# EasyEDA_Circuit_and_PCB.net
KiCad netlist of a schematic drawn in EasyEDA
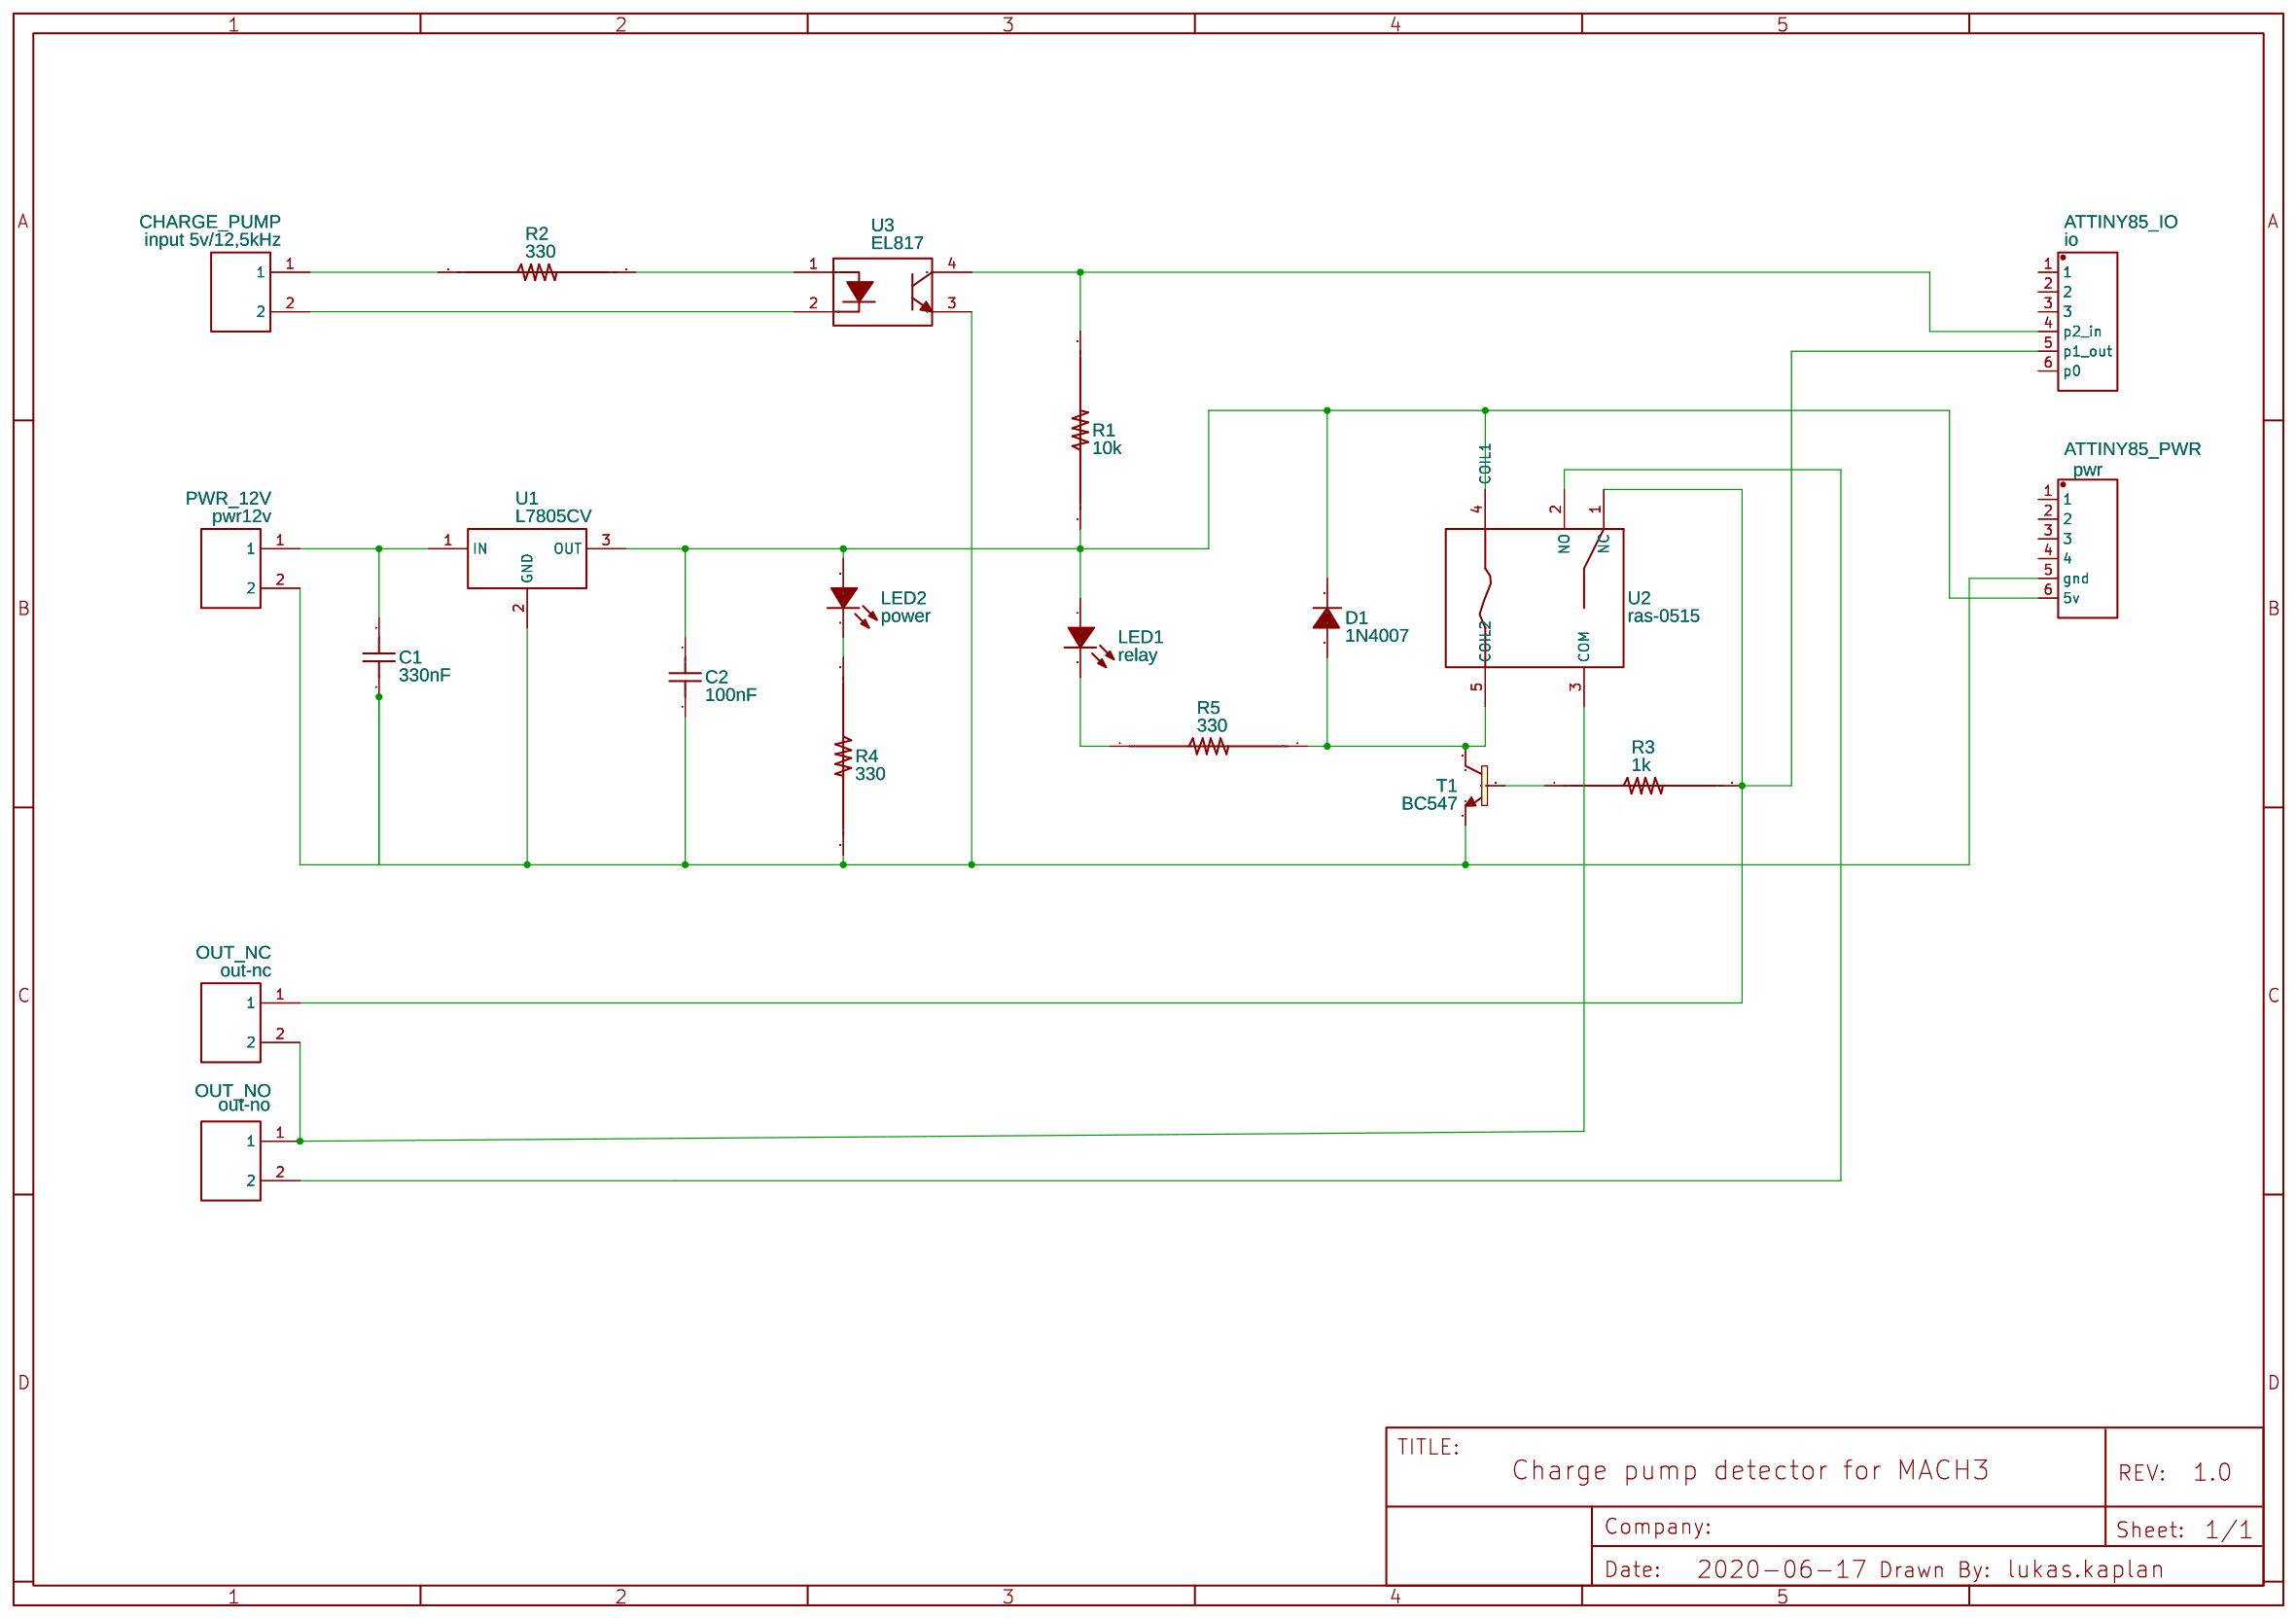
[diagram p0: schematic sheet]

(export (version "E")
  (design (tool "Eeschema 10.0.6"))
  (components
    (comp (ref "ATTINY85_IO")
      (value "io")
      (fields (field (name "BOM_Manufacturer Part") "6pin") (field (name "BOM_Supplier Part") "C350307"))
      (libsource (lib "") (part "2685Y-106CNG1SNA01"))
    )
    (comp (ref "ATTINY85_PWR")
      (value "pwr")
      (fields
        (field (name "BOM_Manufacturer Part") "2685Y-106CNG1SNA01")
        (field (name "BOM_Supplier Part") "C350307")
      )
      (libsource (lib "") (part "2685Y-106CNG1SNA01_1"))
    )
    (comp (ref "C1")
      (value "330nF")
      (fields
        (field (name "BOM_Manufacturer Part") "CT4-0805Y334M500")
        (field (name "BOM_Supplier Part") "C3784")
      )
      (libsource (lib "") (part "CT4-0805Y334M500"))
    )
    (comp (ref "C2")
      (value "100nF")
      (fields
        (field (name "BOM_Manufacturer Part") "CT4-0805Y334M500")
        (field (name "BOM_Supplier Part") "C3784")
      )
      (libsource (lib "") (part "CT4-0805Y334M500"))
    )
    (comp (ref "CHARGE_PUMP")
      (value "input 5v/12,5kHz")
      (fields
        (field (name "BOM_Manufacturer Part") "MKDSN1.5/2-5.08")
        (field (name "BOM_Supplier Part") "C91153")
      )
      (libsource (lib "") (part "MKDSN1.5/2-5.08"))
    )
    (comp (ref "D1")
      (value "1N4007")
      (fields (field (name "BOM_Supplier Part") "C106903"))
      (libsource (lib "") (part "1N4007"))
    )
    (comp (ref "LED1")
      (value "relay")
      (fields
        (field (name "BOM_Manufacturer Part") "DY-333UYGD/SN-A3(EL)")
        (field (name "BOM_Supplier Part") "C396995")
      )
      (libsource (lib "") (part "DY-333UYGD/SN-A3(EL)"))
    )
    (comp (ref "LED2")
      (value "power")
      (fields
        (field (name "BOM_Manufacturer Part") "DY-333UYGD/SN-A3(EL)")
        (field (name "BOM_Supplier Part") "C396995")
      )
      (libsource (lib "") (part "DY-333UYGD/SN-A3(EL)"))
    )
    (comp (ref "OUT_NC")
      (value "out-nc")
      (fields
        (field (name "BOM_Manufacturer Part") "MKDSN1.5/2-5.08")
        (field (name "BOM_Supplier Part") "C91153")
      )
      (libsource (lib "") (part "MKDSN1.5/2-5.08_3"))
    )
    (comp (ref "OUT_NO")
      (value "out-no")
      (fields
        (field (name "BOM_Manufacturer Part") "MKDSN1.5/2-5.08")
        (field (name "BOM_Supplier Part") "C91153")
      )
      (libsource (lib "") (part "MKDSN1.5/2-5.08_1"))
    )
    (comp (ref "PWR_12V")
      (value "pwr12v")
      (fields
        (field (name "BOM_Manufacturer Part") "MKDSN1.5/2-5.08")
        (field (name "BOM_Supplier Part") "C91153")
      )
      (libsource (lib "") (part "MKDSN1.5/2-5.08_2"))
    )
    (comp (ref "R1") (value "10k") (libsource (lib "") (part "RESISTOR_2")))
    (comp (ref "R2") (value "330") (libsource (lib "") (part "RESISTOR")))
    (comp (ref "R3") (value "1k") (libsource (lib "") (part "RESISTOR")))
    (comp (ref "R4") (value "330") (libsource (lib "") (part "RESISTOR_1")))
    (comp (ref "R5") (value "330") (libsource (lib "") (part "RESISTOR")))
    (comp (ref "T1") (value "BC547") (libsource (lib "") (part "BC547")))
    (comp (ref "U1")
      (value "L7805CV")
      (fields (field (name "BOM_Supplier Part") "C111887"))
      (libsource (lib "") (part "L7805CV"))
    )
    (comp (ref "U2") (value "ras-0515") (libsource (lib "") (part "ras-0515")))
    (comp (ref "U3")
      (value "EL817")
      (fields (field (name "BOM_Manufacturer Part") "EL817(C)-F"))
      (libsource (lib "") (part "EL817"))
    )
  )
  (nets
    (net (code "1") (name "Net-(ATTINY85_IO-p1_out)") (class "Default")
      (node (ref "ATTINY85_IO") (pin "5") (pinfunction "p1_out_5") (pintype "unspecified"))
      (node (ref "OUT_NC") (pin "1") (pinfunction "1_1") (pintype "unspecified"))
      (node (ref "R3") (pin "2") (pinfunction "2_2") (pintype "unspecified"))
      (node (ref "U2") (pin "1") (pinfunction "NC_1") (pintype "unspecified"))
    )
    (net (code "2") (name "Net-(ATTINY85_IO-p2_in)") (class "Default")
      (node (ref "ATTINY85_IO") (pin "4") (pinfunction "p2_in_4") (pintype "unspecified"))
      (node (ref "R1") (pin "2") (pinfunction "2_2") (pintype "unspecified"))
      (node (ref "U3") (pin "4") (pinfunction "COL_4") (pintype "unspecified"))
    )
    (net (code "3") (name "Net-(ATTINY85_PWR-5v)") (class "Default")
      (node (ref "ATTINY85_PWR") (pin "6") (pinfunction "5v_6") (pintype "unspecified"))
      (node (ref "C2") (pin "2") (pinfunction "2_2") (pintype "unspecified"))
      (node (ref "D1") (pin "1") (pinfunction "K_1") (pintype "unspecified"))
      (node (ref "LED1") (pin "1") (pinfunction "A_1") (pintype "unspecified"))
      (node (ref "LED2") (pin "1") (pinfunction "A_1") (pintype "unspecified"))
      (node (ref "R1") (pin "1") (pinfunction "1_1") (pintype "unspecified"))
      (node (ref "U1") (pin "3") (pinfunction "OUT_3") (pintype "passive"))
      (node (ref "U2") (pin "4") (pinfunction "COIL1_4") (pintype "unspecified"))
    )
    (net (code "4") (name "Net-(ATTINY85_PWR-gnd)") (class "Default")
      (node (ref "ATTINY85_PWR") (pin "5") (pinfunction "gnd_5") (pintype "unspecified"))
      (node (ref "C1") (pin "1") (pinfunction "1_1") (pintype "unspecified"))
      (node (ref "C2") (pin "1") (pinfunction "1_1") (pintype "unspecified"))
      (node (ref "PWR_12V") (pin "2") (pinfunction "2_2") (pintype "unspecified"))
      (node (ref "R4") (pin "2") (pinfunction "2_2") (pintype "unspecified"))
      (node (ref "T1") (pin "1") (pinfunction "E_1") (pintype "bidirectional"))
      (node (ref "U1") (pin "2") (pinfunction "GND_2") (pintype "passive"))
      (node (ref "U3") (pin "3") (pinfunction "EM_3") (pintype "unspecified"))
    )
    (net (code "5") (name "Net-(CHARGE_PUMP-Pad1)") (class "Default")
      (node (ref "CHARGE_PUMP") (pin "1") (pinfunction "1_1") (pintype "unspecified"))
      (node (ref "R2") (pin "1") (pinfunction "1_1") (pintype "unspecified"))
    )
    (net (code "6") (name "Net-(D1-A)") (class "Default")
      (node (ref "D1") (pin "2") (pinfunction "A_2") (pintype "unspecified"))
      (node (ref "R5") (pin "2") (pinfunction "2_2") (pintype "unspecified"))
      (node (ref "T1") (pin "3") (pinfunction "C_3") (pintype "bidirectional"))
      (node (ref "U2") (pin "5") (pinfunction "COIL2_5") (pintype "unspecified"))
    )
    (net (code "7") (name "Net-(LED1-K)") (class "Default")
      (node (ref "LED1") (pin "2") (pinfunction "K_2") (pintype "unspecified"))
      (node (ref "R5") (pin "1") (pinfunction "1_1") (pintype "unspecified"))
    )
    (net (code "8") (name "Net-(LED2-K)") (class "Default")
      (node (ref "LED2") (pin "2") (pinfunction "K_2") (pintype "unspecified"))
      (node (ref "R4") (pin "1") (pinfunction "1_1") (pintype "unspecified"))
    )
    (net (code "9") (name "Net-(T1-B)") (class "Default")
      (node (ref "R3") (pin "1") (pinfunction "1_1") (pintype "unspecified"))
      (node (ref "T1") (pin "2") (pinfunction "B_2") (pintype "bidirectional"))
    )
    (net (code "10") (name "Net-(U1-IN)") (class "Default")
      (node (ref "C1") (pin "2") (pinfunction "2_2") (pintype "unspecified"))
      (node (ref "PWR_12V") (pin "1") (pinfunction "1_1") (pintype "unspecified"))
      (node (ref "U1") (pin "1") (pinfunction "IN_1") (pintype "passive"))
    )
    (net (code "11") (name "Net-(U2-COM)") (class "Default")
      (node (ref "OUT_NC") (pin "2") (pinfunction "2_2") (pintype "unspecified"))
      (node (ref "OUT_NO") (pin "1") (pinfunction "1_1") (pintype "unspecified"))
      (node (ref "U2") (pin "3") (pinfunction "COM_3") (pintype "unspecified"))
    )
    (net (code "12") (name "Net-(U2-NO)") (class "Default")
      (node (ref "OUT_NO") (pin "2") (pinfunction "2_2") (pintype "unspecified"))
      (node (ref "U2") (pin "2") (pinfunction "NO_2") (pintype "unspecified"))
    )
    (net (code "13") (name "Net-(U3-AN)") (class "Default")
      (node (ref "R2") (pin "2") (pinfunction "2_2") (pintype "unspecified"))
      (node (ref "U3") (pin "1") (pinfunction "AN_1") (pintype "unspecified"))
    )
    (net (code "14") (name "Net-(U3-CAT)") (class "Default")
      (node (ref "CHARGE_PUMP") (pin "2") (pinfunction "2_2") (pintype "unspecified"))
      (node (ref "U3") (pin "2") (pinfunction "CAT_2") (pintype "unspecified"))
    )
    (net (code "15") (name "unconnected-(ATTINY85_IO-Pad1)") (class "Default")
      (node (ref "ATTINY85_IO") (pin "1") (pinfunction "1_1") (pintype "unspecified"))
    )
    (net (code "16") (name "unconnected-(ATTINY85_IO-Pad2)") (class "Default")
      (node (ref "ATTINY85_IO") (pin "2") (pinfunction "2_2") (pintype "unspecified"))
    )
    (net (code "17") (name "unconnected-(ATTINY85_IO-Pad3)") (class "Default")
      (node (ref "ATTINY85_IO") (pin "3") (pinfunction "3_3") (pintype "unspecified"))
    )
    (net (code "18") (name "unconnected-(ATTINY85_IO-p0-Pad6)") (class "Default")
      (node (ref "ATTINY85_IO") (pin "6") (pinfunction "p0_6") (pintype "unspecified"))
    )
    (net (code "19") (name "unconnected-(ATTINY85_PWR-Pad1)") (class "Default")
      (node (ref "ATTINY85_PWR") (pin "1") (pinfunction "1_1") (pintype "unspecified"))
    )
    (net (code "20") (name "unconnected-(ATTINY85_PWR-Pad2)") (class "Default")
      (node (ref "ATTINY85_PWR") (pin "2") (pinfunction "2_2") (pintype "unspecified"))
    )
    (net (code "21") (name "unconnected-(ATTINY85_PWR-Pad3)") (class "Default")
      (node (ref "ATTINY85_PWR") (pin "3") (pinfunction "3_3") (pintype "unspecified"))
    )
    (net (code "22") (name "unconnected-(ATTINY85_PWR-Pad4)") (class "Default")
      (node (ref "ATTINY85_PWR") (pin "4") (pinfunction "4_4") (pintype "unspecified"))
    )
  )
)
